# Ring_4_A.net
KiCad netlist of a schematic drawn in Altium Designer
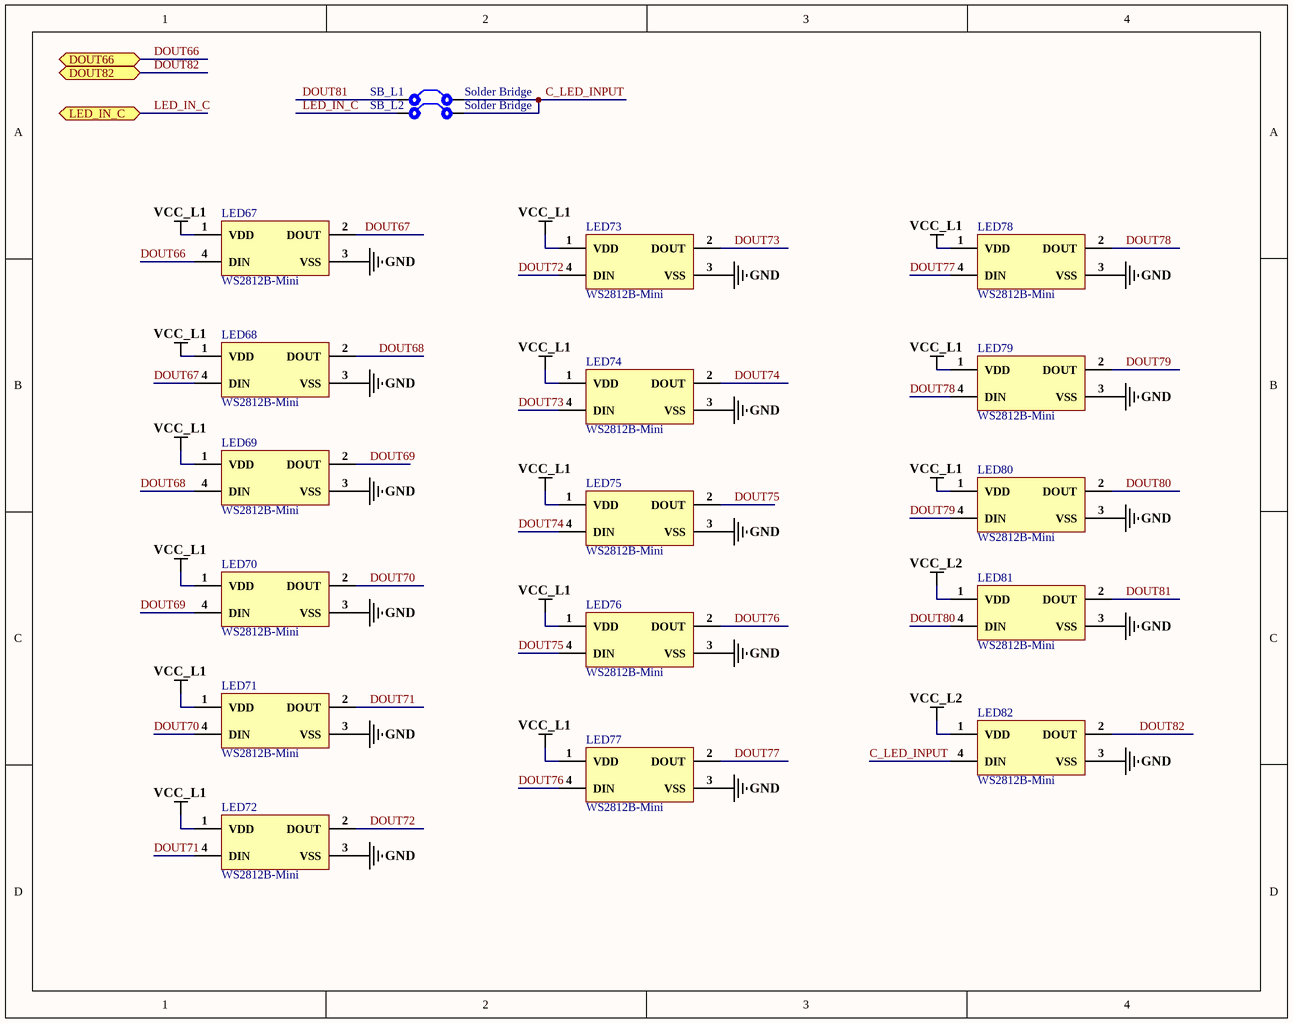
[diagram p0: Ring 4_A.SchDoc]

(export (version "E")
  (design (tool "Eeschema 10.0.6"))
  (components
    (comp (ref "LED67")
      (value "WS2812B-Mini")
      (footprint "WS2812B-Mini")
      (description "SMD,3.5x3.5mm Light Emitting Diodes (LED) RoHS")
      (fields (field (name "MANUFACTURER") "Worldsemi"))
      (libsource (lib "TT_IntLib") (part "WS2812B-Mini"))
    )
    (comp (ref "LED68")
      (value "WS2812B-Mini")
      (footprint "WS2812B-Mini")
      (description "SMD,3.5x3.5mm Light Emitting Diodes (LED) RoHS")
      (fields (field (name "MANUFACTURER") "Worldsemi"))
      (libsource (lib "TT_IntLib") (part "WS2812B-Mini"))
    )
    (comp (ref "LED69")
      (value "WS2812B-Mini")
      (footprint "WS2812B-Mini")
      (description "SMD,3.5x3.5mm Light Emitting Diodes (LED) RoHS")
      (fields (field (name "MANUFACTURER") "Worldsemi"))
      (libsource (lib "TT_IntLib") (part "WS2812B-Mini"))
    )
    (comp (ref "LED70")
      (value "WS2812B-Mini")
      (footprint "WS2812B-Mini")
      (description "SMD,3.5x3.5mm Light Emitting Diodes (LED) RoHS")
      (fields (field (name "MANUFACTURER") "Worldsemi"))
      (libsource (lib "TT_IntLib") (part "WS2812B-Mini"))
    )
    (comp (ref "LED71")
      (value "WS2812B-Mini")
      (footprint "WS2812B-Mini")
      (description "SMD,3.5x3.5mm Light Emitting Diodes (LED) RoHS")
      (fields (field (name "MANUFACTURER") "Worldsemi"))
      (libsource (lib "TT_IntLib") (part "WS2812B-Mini"))
    )
    (comp (ref "LED72")
      (value "WS2812B-Mini")
      (footprint "WS2812B-Mini")
      (description "SMD,3.5x3.5mm Light Emitting Diodes (LED) RoHS")
      (fields (field (name "MANUFACTURER") "Worldsemi"))
      (libsource (lib "TT_IntLib") (part "WS2812B-Mini"))
    )
    (comp (ref "LED73")
      (value "WS2812B-Mini")
      (footprint "WS2812B-Mini")
      (description "SMD,3.5x3.5mm Light Emitting Diodes (LED) RoHS")
      (fields (field (name "MANUFACTURER") "Worldsemi"))
      (libsource (lib "TT_IntLib") (part "WS2812B-Mini"))
    )
    (comp (ref "LED74")
      (value "WS2812B-Mini")
      (footprint "WS2812B-Mini")
      (description "SMD,3.5x3.5mm Light Emitting Diodes (LED) RoHS")
      (fields (field (name "MANUFACTURER") "Worldsemi"))
      (libsource (lib "TT_IntLib") (part "WS2812B-Mini"))
    )
    (comp (ref "LED75")
      (value "WS2812B-Mini")
      (footprint "WS2812B-Mini")
      (description "SMD,3.5x3.5mm Light Emitting Diodes (LED) RoHS")
      (fields (field (name "MANUFACTURER") "Worldsemi"))
      (libsource (lib "TT_IntLib") (part "WS2812B-Mini"))
    )
    (comp (ref "LED76")
      (value "WS2812B-Mini")
      (footprint "WS2812B-Mini")
      (description "SMD,3.5x3.5mm Light Emitting Diodes (LED) RoHS")
      (fields (field (name "MANUFACTURER") "Worldsemi"))
      (libsource (lib "TT_IntLib") (part "WS2812B-Mini"))
    )
    (comp (ref "LED77")
      (value "WS2812B-Mini")
      (footprint "WS2812B-Mini")
      (description "SMD,3.5x3.5mm Light Emitting Diodes (LED) RoHS")
      (fields (field (name "MANUFACTURER") "Worldsemi"))
      (libsource (lib "TT_IntLib") (part "WS2812B-Mini"))
    )
    (comp (ref "LED78")
      (value "WS2812B-Mini")
      (footprint "WS2812B-Mini")
      (description "SMD,3.5x3.5mm Light Emitting Diodes (LED) RoHS")
      (fields (field (name "MANUFACTURER") "Worldsemi"))
      (libsource (lib "TT_IntLib") (part "WS2812B-Mini"))
    )
    (comp (ref "LED79")
      (value "WS2812B-Mini")
      (footprint "WS2812B-Mini")
      (description "SMD,3.5x3.5mm Light Emitting Diodes (LED) RoHS")
      (fields (field (name "MANUFACTURER") "Worldsemi"))
      (libsource (lib "TT_IntLib") (part "WS2812B-Mini"))
    )
    (comp (ref "LED80")
      (value "WS2812B-Mini")
      (footprint "WS2812B-Mini")
      (description "SMD,3.5x3.5mm Light Emitting Diodes (LED) RoHS")
      (fields (field (name "MANUFACTURER") "Worldsemi"))
      (libsource (lib "TT_IntLib") (part "WS2812B-Mini"))
    )
    (comp (ref "LED81")
      (value "WS2812B-Mini")
      (footprint "WS2812B-Mini")
      (description "SMD,3.5x3.5mm Light Emitting Diodes (LED) RoHS")
      (fields (field (name "MANUFACTURER") "Worldsemi"))
      (libsource (lib "TT_IntLib") (part "WS2812B-Mini"))
    )
    (comp (ref "LED82")
      (value "WS2812B-Mini")
      (footprint "WS2812B-Mini")
      (description "SMD,3.5x3.5mm Light Emitting Diodes (LED) RoHS")
      (fields (field (name "MANUFACTURER") "Worldsemi"))
      (libsource (lib "TT_IntLib") (part "WS2812B-Mini"))
    )
    (comp (ref "SB_L1")
      (value "Solder Bridge")
      (footprint "Solder Bridge")
      (description "Solder Bridge ON")
      (libsource (lib "TT_IntLib") (part "Solder Bridge"))
    )
    (comp (ref "SB_L2")
      (value "Solder Bridge")
      (footprint "Solder Bridge")
      (description "Solder Bridge ON")
      (libsource (lib "TT_IntLib") (part "Solder Bridge"))
    )
  )
  (nets
    (net (code "1") (name "/C_LED_INPUT") (class "Default")
      (node (ref "LED82") (pin "4") (pinfunction "DIN_4") (pintype "passive"))
      (node (ref "SB_L1") (pin "2") (pinfunction "2_2") (pintype "passive"))
      (node (ref "SB_L2") (pin "2") (pinfunction "2_2") (pintype "passive"))
    )
    (net (code "2") (name "/DOUT66") (class "Default")
      (node (ref "LED67") (pin "4") (pinfunction "DIN_4") (pintype "passive"))
    )
    (net (code "3") (name "/DOUT67") (class "Default")
      (node (ref "LED67") (pin "2") (pinfunction "DOUT_2") (pintype "passive"))
      (node (ref "LED68") (pin "4") (pinfunction "DIN_4") (pintype "passive"))
    )
    (net (code "4") (name "/DOUT68") (class "Default")
      (node (ref "LED68") (pin "2") (pinfunction "DOUT_2") (pintype "passive"))
      (node (ref "LED69") (pin "4") (pinfunction "DIN_4") (pintype "passive"))
    )
    (net (code "5") (name "/DOUT69") (class "Default")
      (node (ref "LED69") (pin "2") (pinfunction "DOUT_2") (pintype "passive"))
      (node (ref "LED70") (pin "4") (pinfunction "DIN_4") (pintype "passive"))
    )
    (net (code "6") (name "/DOUT70") (class "Default")
      (node (ref "LED70") (pin "2") (pinfunction "DOUT_2") (pintype "passive"))
      (node (ref "LED71") (pin "4") (pinfunction "DIN_4") (pintype "passive"))
    )
    (net (code "7") (name "/DOUT71") (class "Default")
      (node (ref "LED71") (pin "2") (pinfunction "DOUT_2") (pintype "passive"))
      (node (ref "LED72") (pin "4") (pinfunction "DIN_4") (pintype "passive"))
    )
    (net (code "8") (name "/DOUT72") (class "Default")
      (node (ref "LED72") (pin "2") (pinfunction "DOUT_2") (pintype "passive"))
      (node (ref "LED73") (pin "4") (pinfunction "DIN_4") (pintype "passive"))
    )
    (net (code "9") (name "/DOUT73") (class "Default")
      (node (ref "LED73") (pin "2") (pinfunction "DOUT_2") (pintype "passive"))
      (node (ref "LED74") (pin "4") (pinfunction "DIN_4") (pintype "passive"))
    )
    (net (code "10") (name "/DOUT74") (class "Default")
      (node (ref "LED74") (pin "2") (pinfunction "DOUT_2") (pintype "passive"))
      (node (ref "LED75") (pin "4") (pinfunction "DIN_4") (pintype "passive"))
    )
    (net (code "11") (name "/DOUT75") (class "Default")
      (node (ref "LED75") (pin "2") (pinfunction "DOUT_2") (pintype "passive"))
      (node (ref "LED76") (pin "4") (pinfunction "DIN_4") (pintype "passive"))
    )
    (net (code "12") (name "/DOUT76") (class "Default")
      (node (ref "LED76") (pin "2") (pinfunction "DOUT_2") (pintype "passive"))
      (node (ref "LED77") (pin "4") (pinfunction "DIN_4") (pintype "passive"))
    )
    (net (code "13") (name "/DOUT77") (class "Default")
      (node (ref "LED77") (pin "2") (pinfunction "DOUT_2") (pintype "passive"))
      (node (ref "LED78") (pin "4") (pinfunction "DIN_4") (pintype "passive"))
    )
    (net (code "14") (name "/DOUT78") (class "Default")
      (node (ref "LED78") (pin "2") (pinfunction "DOUT_2") (pintype "passive"))
      (node (ref "LED79") (pin "4") (pinfunction "DIN_4") (pintype "passive"))
    )
    (net (code "15") (name "/DOUT79") (class "Default")
      (node (ref "LED79") (pin "2") (pinfunction "DOUT_2") (pintype "passive"))
      (node (ref "LED80") (pin "4") (pinfunction "DIN_4") (pintype "passive"))
    )
    (net (code "16") (name "/DOUT80") (class "Default")
      (node (ref "LED80") (pin "2") (pinfunction "DOUT_2") (pintype "passive"))
      (node (ref "LED81") (pin "4") (pinfunction "DIN_4") (pintype "passive"))
    )
    (net (code "17") (name "/DOUT81") (class "Default")
      (node (ref "LED81") (pin "2") (pinfunction "DOUT_2") (pintype "passive"))
      (node (ref "SB_L1") (pin "1") (pinfunction "1_1") (pintype "passive"))
    )
    (net (code "18") (name "/DOUT82") (class "Default")
      (node (ref "LED82") (pin "2") (pinfunction "DOUT_2") (pintype "passive"))
    )
    (net (code "19") (name "/LED_IN_C") (class "Default")
      (node (ref "SB_L2") (pin "1") (pinfunction "1_1") (pintype "passive"))
    )
    (net (code "20") (name "GND") (class "Default")
      (node (ref "LED67") (pin "3") (pinfunction "VSS_3") (pintype "passive"))
      (node (ref "LED68") (pin "3") (pinfunction "VSS_3") (pintype "passive"))
      (node (ref "LED69") (pin "3") (pinfunction "VSS_3") (pintype "passive"))
      (node (ref "LED70") (pin "3") (pinfunction "VSS_3") (pintype "passive"))
      (node (ref "LED71") (pin "3") (pinfunction "VSS_3") (pintype "passive"))
      (node (ref "LED72") (pin "3") (pinfunction "VSS_3") (pintype "passive"))
      (node (ref "LED73") (pin "3") (pinfunction "VSS_3") (pintype "passive"))
      (node (ref "LED74") (pin "3") (pinfunction "VSS_3") (pintype "passive"))
      (node (ref "LED75") (pin "3") (pinfunction "VSS_3") (pintype "passive"))
      (node (ref "LED76") (pin "3") (pinfunction "VSS_3") (pintype "passive"))
      (node (ref "LED77") (pin "3") (pinfunction "VSS_3") (pintype "passive"))
      (node (ref "LED78") (pin "3") (pinfunction "VSS_3") (pintype "passive"))
      (node (ref "LED79") (pin "3") (pinfunction "VSS_3") (pintype "passive"))
      (node (ref "LED80") (pin "3") (pinfunction "VSS_3") (pintype "passive"))
      (node (ref "LED81") (pin "3") (pinfunction "VSS_3") (pintype "passive"))
      (node (ref "LED82") (pin "3") (pinfunction "VSS_3") (pintype "passive"))
    )
    (net (code "21") (name "VCC_L1") (class "Default")
      (node (ref "LED67") (pin "1") (pinfunction "VDD_1") (pintype "passive"))
      (node (ref "LED68") (pin "1") (pinfunction "VDD_1") (pintype "passive"))
      (node (ref "LED69") (pin "1") (pinfunction "VDD_1") (pintype "passive"))
      (node (ref "LED70") (pin "1") (pinfunction "VDD_1") (pintype "passive"))
      (node (ref "LED71") (pin "1") (pinfunction "VDD_1") (pintype "passive"))
      (node (ref "LED72") (pin "1") (pinfunction "VDD_1") (pintype "passive"))
      (node (ref "LED73") (pin "1") (pinfunction "VDD_1") (pintype "passive"))
      (node (ref "LED74") (pin "1") (pinfunction "VDD_1") (pintype "passive"))
      (node (ref "LED75") (pin "1") (pinfunction "VDD_1") (pintype "passive"))
      (node (ref "LED76") (pin "1") (pinfunction "VDD_1") (pintype "passive"))
      (node (ref "LED77") (pin "1") (pinfunction "VDD_1") (pintype "passive"))
      (node (ref "LED78") (pin "1") (pinfunction "VDD_1") (pintype "passive"))
      (node (ref "LED79") (pin "1") (pinfunction "VDD_1") (pintype "passive"))
      (node (ref "LED80") (pin "1") (pinfunction "VDD_1") (pintype "passive"))
    )
    (net (code "22") (name "VCC_L2") (class "Default")
      (node (ref "LED81") (pin "1") (pinfunction "VDD_1") (pintype "passive"))
      (node (ref "LED82") (pin "1") (pinfunction "VDD_1") (pintype "passive"))
    )
  )
)
